# RF_filter.net
KiCad netlist of a schematic drawn in Altium Designer
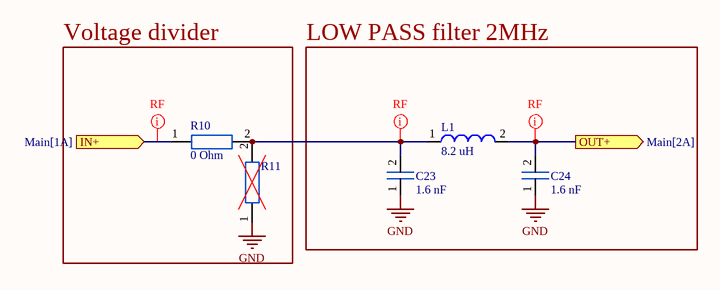
[diagram p0: RF_filter.SchDoc]

(export (version "E")
  (design (tool "Eeschema 10.0.6"))
  (components
    (comp (ref "C23")
      (value "1.6 nF")
      (footprint "0402_footprint")
      (description "0402 capacitor")
      (libsource (lib "Schlib1") (part "Capacitor_0402"))
    )
    (comp (ref "C24")
      (value "1.6 nF")
      (footprint "0402_footprint")
      (description "0402 capacitor")
      (libsource (lib "Schlib1") (part "Capacitor_0402"))
    )
    (comp (ref "L1")
      (value "8.2 uH")
      (footprint "0603_FOOTPRINT")
      (description "0603 inductor")
      (libsource (lib "Schlib1") (part "Inductor_0603"))
    )
    (comp (ref "R10")
      (value "0 Ohm")
      (footprint "0402_footprint")
      (libsource (lib "Schlib1") (part "Resistor_0402"))
    )
    (comp (ref "R11")
      (value "~")
      (footprint "0402_footprint")
      (libsource (lib "Schlib1") (part "Resistor_0402"))
    )
  )
  (nets
    (net (code "1") (name "/IN+") (class "Default")
      (node (ref "R10") (pin "1") (pinfunction "1_1") (pintype "passive"))
    )
    (net (code "2") (name "/OUT+") (class "Default")
      (node (ref "C24") (pin "2") (pinfunction "2_2") (pintype "passive"))
      (node (ref "L1") (pin "2") (pinfunction "2_2") (pintype "passive"))
    )
    (net (code "3") (name "GND") (class "Default")
      (node (ref "C23") (pin "1") (pinfunction "1_1") (pintype "passive"))
      (node (ref "C24") (pin "1") (pinfunction "1_1") (pintype "passive"))
      (node (ref "R11") (pin "1") (pinfunction "1_1") (pintype "passive"))
    )
    (net (code "4") (name "Net-(C23-Pad2)") (class "Default")
      (node (ref "C23") (pin "2") (pinfunction "2_2") (pintype "passive"))
      (node (ref "L1") (pin "1") (pinfunction "1_1") (pintype "passive"))
      (node (ref "R10") (pin "2") (pinfunction "2_2") (pintype "passive"))
      (node (ref "R11") (pin "2") (pinfunction "2_2") (pintype "passive"))
    )
  )
)
